# hello_slave.net
KiCad netlist of a schematic drawn in EAGLE
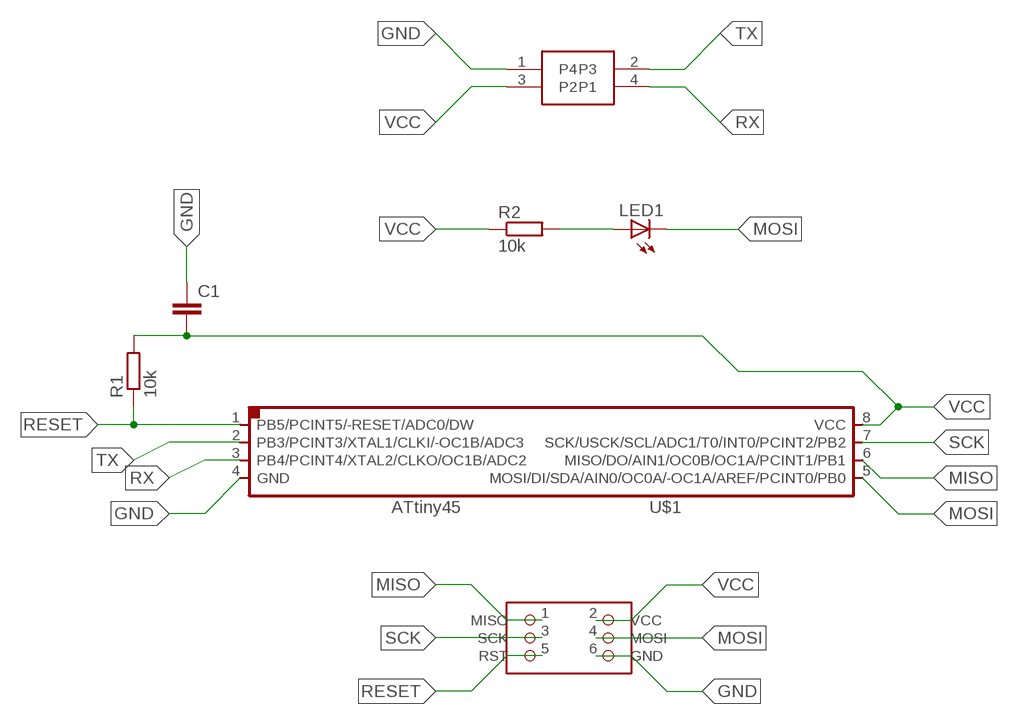
[diagram p0: schematic, sheet 1]

(export (version "E")
  (design (tool "Eeschema 10.0.6"))
  (components
    (comp (ref "C1") (value "C") (footprint "eagle-import:C0805") (libsource (lib "eagle-import") (part "C")))
    (comp (ref "LED1")
      (value "LED_E")
      (footprint "eagle-import:LED_1206")
      (libsource (lib "eagle-import") (part "LED_E"))
    )
    (comp (ref "R1")
      (value "10k")
      (footprint "eagle-import:R0805")
      (libsource (lib "eagle-import") (part "R"))
    )
    (comp (ref "R2")
      (value "10k")
      (footprint "eagle-import:R0805")
      (libsource (lib "eagle-import") (part "R"))
    )
    (comp (ref "U$1")
      (value "ATTINY45SI")
      (footprint "eagle-import:SOIC8")
      (libsource (lib "eagle-import") (part "ATTINY45SI"))
    )
    (comp (ref "U$2")
      (value "AVRISPSMD")
      (footprint "eagle-import:2X03SMD")
      (libsource (lib "eagle-import") (part "AVRISPSMD"))
    )
    (comp (ref "U$4")
      (value "4PIN-SMD-CONNECTOR")
      (footprint "eagle-import:2X02SMD")
      (libsource (lib "eagle-import") (part "4PIN-SMD-CONNECTOR"))
    )
  )
  (nets
    (net (code "1") (name "GND") (class "Default")
      (node (ref "C1") (pin "1") (pinfunction "1_1") (pintype "passive"))
      (node (ref "U$1") (pin "4") (pinfunction "GND_4") (pintype "bidirectional"))
      (node (ref "U$2") (pin "6") (pinfunction "GND_6") (pintype "passive"))
      (node (ref "U$4") (pin "1") (pinfunction "P4_1") (pintype "bidirectional"))
    )
    (net (code "2") (name "MISO") (class "Default")
      (node (ref "U$1") (pin "6") (pinfunction "MISO/DO/AIN1/OC0B/OC1A/PCINT1/PB1_6") (pintype "bidirectional"))
      (node (ref "U$2") (pin "1") (pinfunction "MISO_1") (pintype "passive"))
    )
    (net (code "3") (name "MOSI") (class "Default")
      (node (ref "LED1") (pin "C") (pinfunction "C_C") (pintype "passive"))
      (node (ref "U$1") (pin "5") (pinfunction "MOSI/DI/SDA/AIN0/OC0A/-OC1A/AREF/PCINT0/PB0_5") (pintype "bidirectional"))
      (node (ref "U$2") (pin "4") (pinfunction "MOSI_4") (pintype "passive"))
    )
    (net (code "4") (name "Net-(LED1-PadA)") (class "Default")
      (node (ref "LED1") (pin "A") (pinfunction "A_A") (pintype "passive"))
      (node (ref "R2") (pin "2") (pinfunction "2_2") (pintype "passive"))
    )
    (net (code "5") (name "RESET") (class "Default")
      (node (ref "R1") (pin "1") (pinfunction "1_1") (pintype "passive"))
      (node (ref "U$1") (pin "1") (pinfunction "PB5/PCINT5/-RESET/ADC0/DW_1") (pintype "bidirectional"))
      (node (ref "U$2") (pin "5") (pinfunction "RST_5") (pintype "passive"))
    )
    (net (code "6") (name "RX") (class "Default")
      (node (ref "U$1") (pin "3") (pinfunction "PB4/PCINT4/XTAL2/CLKO/OC1B/ADC2_3") (pintype "bidirectional"))
      (node (ref "U$4") (pin "4") (pinfunction "P1_4") (pintype "bidirectional"))
    )
    (net (code "7") (name "SCK") (class "Default")
      (node (ref "U$1") (pin "7") (pinfunction "SCK/USCK/SCL/ADC1/T0/INT0/PCINT2/PB2_7") (pintype "bidirectional"))
      (node (ref "U$2") (pin "3") (pinfunction "SCK_3") (pintype "passive"))
    )
    (net (code "8") (name "TX") (class "Default")
      (node (ref "U$1") (pin "2") (pinfunction "PB3/PCINT3/XTAL1/CLKI/-OC1B/ADC3_2") (pintype "bidirectional"))
      (node (ref "U$4") (pin "2") (pinfunction "P3_2") (pintype "bidirectional"))
    )
    (net (code "9") (name "VCC") (class "Default")
      (node (ref "C1") (pin "2") (pinfunction "2_2") (pintype "passive"))
      (node (ref "R1") (pin "2") (pinfunction "2_2") (pintype "passive"))
      (node (ref "R2") (pin "1") (pinfunction "1_1") (pintype "passive"))
      (node (ref "U$1") (pin "8") (pinfunction "VCC_8") (pintype "bidirectional"))
      (node (ref "U$2") (pin "2") (pinfunction "VCC_2") (pintype "passive"))
      (node (ref "U$4") (pin "3") (pinfunction "P2_3") (pintype "bidirectional"))
    )
  )
)
